# Oscillators.net
KiCad netlist of a schematic drawn in Altium Designer
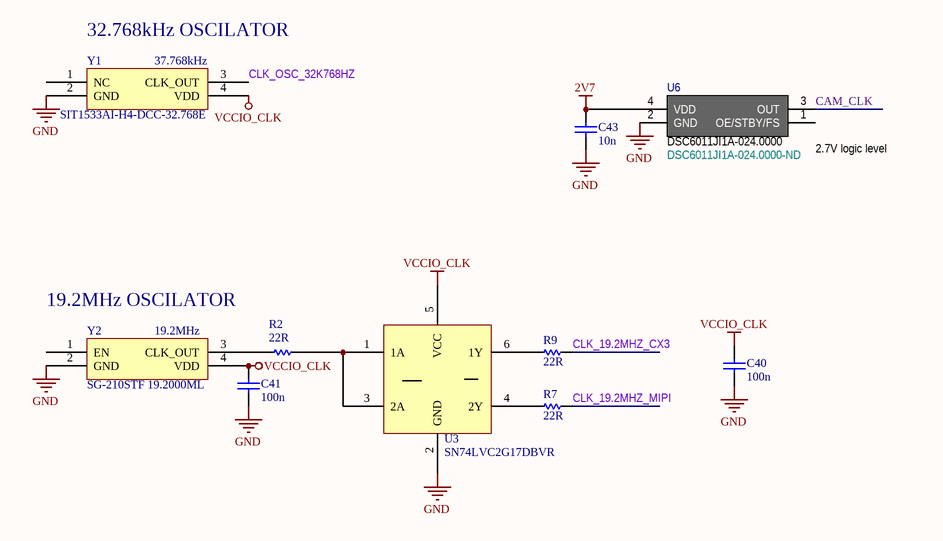
[diagram p0: Oscillators.SchDoc]

(export (version "E")
  (design (tool "Eeschema 10.0.6"))
  (components
    (comp (ref "C40")
      (value "100n")
      (footprint "CAPC0603N")
      (description "Capacitor (Semiconductor SIM Model)")
      (fields (field (name "PUBLISHER") "Altium Limited"))
      (libsource (lib "Miscellaneous Devices") (part "Cap Semi"))
    )
    (comp (ref "C41")
      (value "100n")
      (footprint "CAPC0603N")
      (description "Capacitor (Semiconductor SIM Model)")
      (fields (field (name "PUBLISHER") "Altium Limited"))
      (libsource (lib "Miscellaneous Devices") (part "Cap Semi"))
    )
    (comp (ref "C43")
      (value "10n")
      (footprint "CAPC0603N")
      (description "Capacitor (Semiconductor SIM Model)")
      (fields (field (name "PUBLISHER") "Altium Limited"))
      (libsource (lib "Miscellaneous Devices") (part "Cap Semi"))
    )
    (comp (ref "R2")
      (value "22R")
      (footprint "RESC0603N")
      (description "Semiconductor Resistor")
      (fields (field (name "PUBLISHER") "Altium Limited"))
      (libsource (lib "Miscellaneous Devices") (part "Res Semi"))
    )
    (comp (ref "R7")
      (value "22R")
      (footprint "RESC0603N")
      (description "Semiconductor Resistor")
      (fields (field (name "PUBLISHER") "Altium Limited"))
      (libsource (lib "Miscellaneous Devices") (part "Res Semi"))
    )
    (comp (ref "R9")
      (value "22R")
      (footprint "RESC0603N")
      (description "Semiconductor Resistor")
      (fields (field (name "PUBLISHER") "Altium Limited"))
      (libsource (lib "Miscellaneous Devices") (part "Res Semi"))
    )
    (comp (ref "U3")
      (value "SN74LVC2G17DBVR")
      (footprint "SOT-23_A_N")
      (libsource (lib "CX3_Camera") (part "SN74LVC2G17DBVR"))
    )
    (comp (ref "U6")
      (value "DSC6011JI1A-024.0000")
      (footprint "XTAL2520-4")
      (description "OSC MEMS 24.0000MHZ CMOS SMD")
      (fields
        (field (name "MANUFACTURER") "Microchip Technology")
        (field (name "SUPPLIER PART NUMBER 1") "DSC6011JI1A-024.0000-ND")
      )
      (libsource (lib "Microchip Oscillator") (part "DSC6011JI1A-024.0000"))
    )
    (comp (ref "Y1")
      (value "SIT1533AI-H4-DCC-32.768E")
      (footprint "SiT1533")
      (fields (field (name "ALTIUM_VALUE") "37.768kHz"))
      (libsource (lib "CX3_Camera") (part "OSCILATOR_32kHz"))
    )
    (comp (ref "Y2")
      (value "SG-210STF 19.2000ML")
      (footprint "SG5032")
      (fields (field (name "ALTIUM_VALUE") "19.2MHz"))
      (libsource (lib "CX3_Camera") (part "OSCILLATOR"))
    )
  )
  (nets
    (net (code "1") (name "/CAM_CLK") (class "Default")
      (node (ref "U6") (pin "3") (pinfunction "OUT_3") (pintype "power_in"))
    )
    (net (code "2") (name "/CLK_19.2MHZ_CX3") (class "Default")
      (node (ref "R9") (pin "1") (pinfunction "1_1") (pintype "passive"))
    )
    (net (code "3") (name "/CLK_19.2MHZ_MIPI") (class "Default")
      (node (ref "R7") (pin "1") (pinfunction "1_1") (pintype "passive"))
    )
    (net (code "4") (name "/CLK_OSC_32K768HZ") (class "Default")
      (node (ref "Y1") (pin "3") (pinfunction "CLK_OUT_3") (pintype "passive"))
    )
    (net (code "5") (name "2V7") (class "Default")
      (node (ref "C43") (pin "2") (pinfunction "2_2") (pintype "passive"))
      (node (ref "U6") (pin "4") (pinfunction "VDD_4") (pintype "power_in"))
    )
    (net (code "6") (name "GND") (class "Default")
      (node (ref "C40") (pin "2") (pinfunction "2_2") (pintype "passive"))
      (node (ref "C41") (pin "2") (pinfunction "2_2") (pintype "passive"))
      (node (ref "C43") (pin "1") (pinfunction "1_1") (pintype "passive"))
      (node (ref "U3") (pin "2") (pinfunction "GND_2") (pintype "passive"))
      (node (ref "U6") (pin "2") (pinfunction "GND_2") (pintype "power_in"))
      (node (ref "Y1") (pin "2") (pinfunction "GND_2") (pintype "passive"))
      (node (ref "Y2") (pin "2") (pinfunction "GND_2") (pintype "passive"))
    )
    (net (code "7") (name "Net-(U3-1A)") (class "Default")
      (node (ref "R2") (pin "2") (pinfunction "2_2") (pintype "passive"))
      (node (ref "U3") (pin "1") (pinfunction "1A_1") (pintype "passive"))
      (node (ref "U3") (pin "3") (pinfunction "2A_3") (pintype "passive"))
    )
    (net (code "8") (name "Net-(U3-1Y)") (class "Default")
      (node (ref "R9") (pin "2") (pinfunction "2_2") (pintype "passive"))
      (node (ref "U3") (pin "6") (pinfunction "1Y_6") (pintype "passive"))
    )
    (net (code "9") (name "Net-(U3-2Y)") (class "Default")
      (node (ref "R7") (pin "2") (pinfunction "2_2") (pintype "passive"))
      (node (ref "U3") (pin "4") (pinfunction "2Y_4") (pintype "passive"))
    )
    (net (code "10") (name "Net-(Y2-CLK_OUT)") (class "Default")
      (node (ref "R2") (pin "1") (pinfunction "1_1") (pintype "passive"))
      (node (ref "Y2") (pin "3") (pinfunction "CLK_OUT_3") (pintype "passive"))
    )
    (net (code "11") (name "VCCIO_CLK") (class "Default")
      (node (ref "C40") (pin "1") (pinfunction "1_1") (pintype "passive"))
      (node (ref "C41") (pin "1") (pinfunction "1_1") (pintype "passive"))
      (node (ref "U3") (pin "5") (pinfunction "VCC_5") (pintype "passive"))
      (node (ref "Y1") (pin "4") (pinfunction "VDD_4") (pintype "passive"))
      (node (ref "Y2") (pin "4") (pinfunction "VDD_4") (pintype "passive"))
    )
    (net (code "12") (name "unconnected-(U6-OE{slash}STBY{slash}FS-Pad1)") (class "Default")
      (node (ref "U6") (pin "1") (pinfunction "OE/STBY/FS_1") (pintype "power_in"))
    )
    (net (code "13") (name "unconnected-(Y1-NC-Pad1)") (class "Default")
      (node (ref "Y1") (pin "1") (pinfunction "NC_1") (pintype "passive"))
    )
    (net (code "14") (name "unconnected-(Y2-EN-Pad1)") (class "Default")
      (node (ref "Y2") (pin "1") (pinfunction "EN_1") (pintype "passive"))
    )
  )
)
